# Schematic.net
KiCad netlist of a schematic drawn in EasyEDA
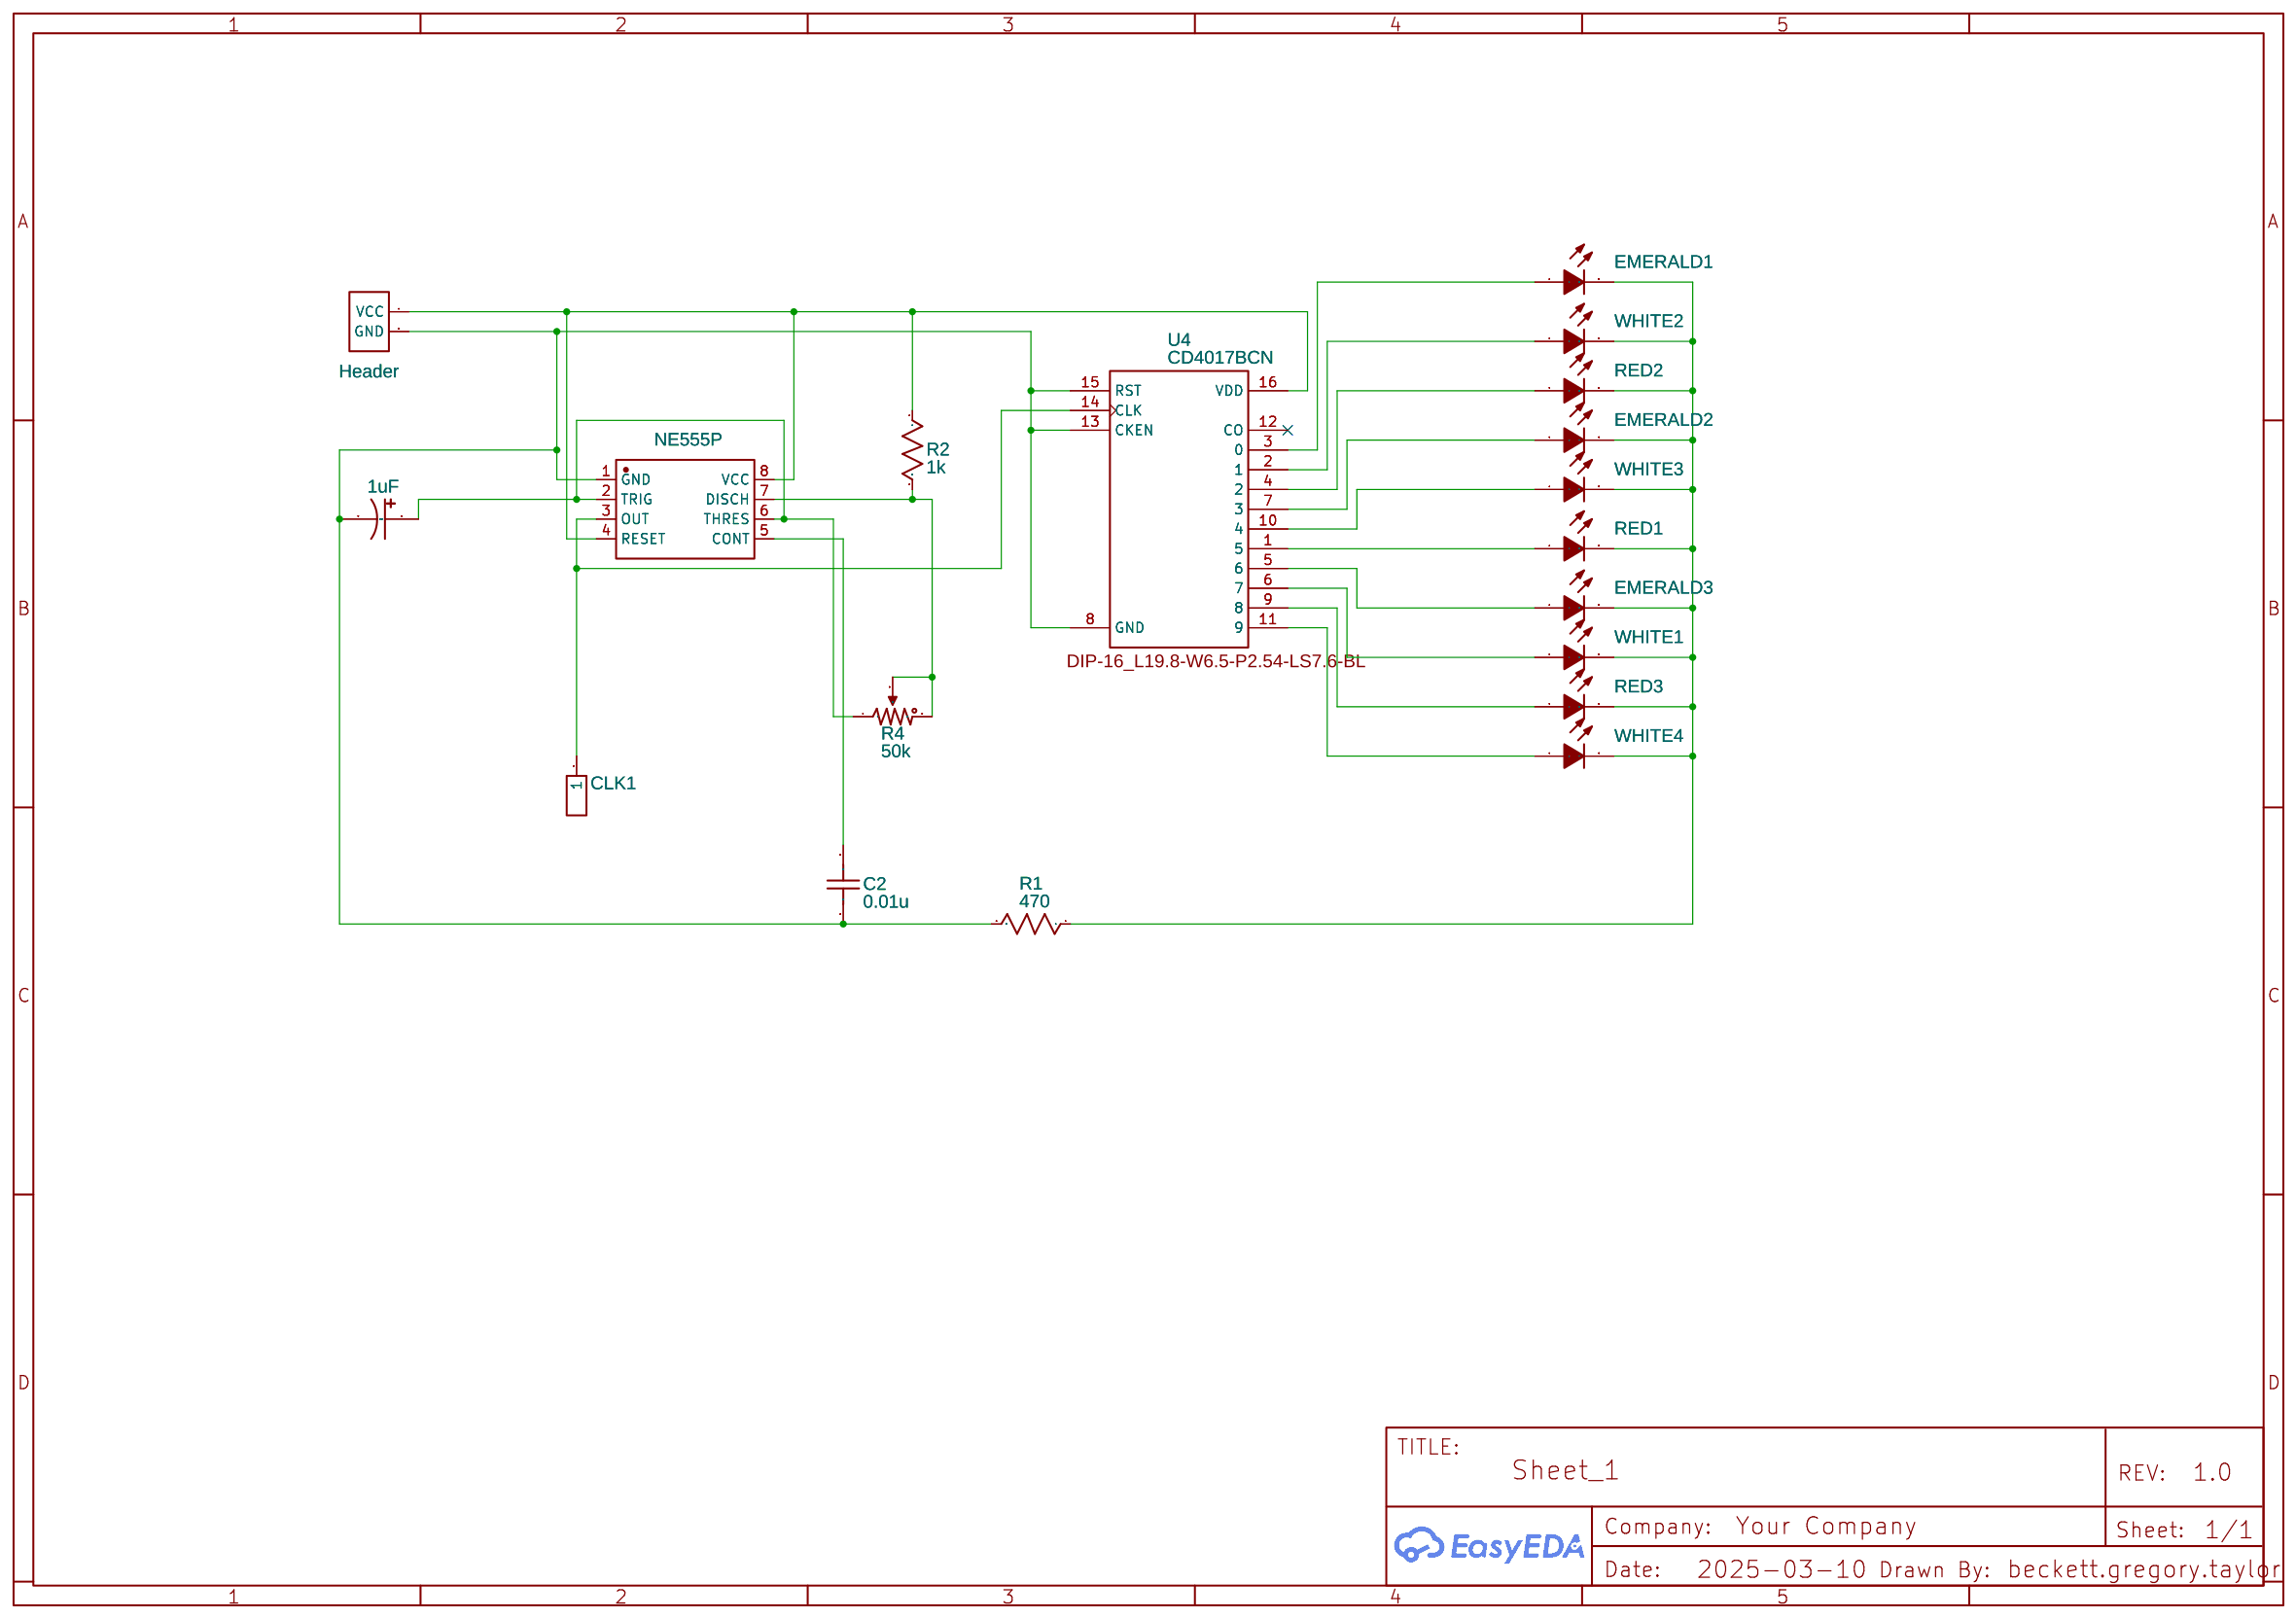
[diagram p0: schematic sheet]

(export (version "E")
  (design (tool "Eeschema 10.0.6"))
  (components
    (comp (ref "C1")
      (value "1uF")
      (fields (field (name "Manufacturer Part") "UVZ1H010MDD") (field (name "Manufacturer") "Nichicon(尼吉康)"))
      (libsource (lib "") (part "UVZ1H010MDD"))
    )
    (comp (ref "C2") (value "0.01u") (libsource (lib "") (part "C_0603_US")))
    (comp (ref "CLK1")
      (value "C81276")
      (fields
        (field (name "Manufacturer Part") "2.54-1*1P针")
        (field (name "Manufacturer") "BOOMELE(Boom Precision Elec)")
      )
      (libsource (lib "") (part "Header-Male-2.54_1x1"))
    )
    (comp (ref "EMERALD1") (value "LED_5MM") (libsource (lib "") (part "LED_5MM_2")))
    (comp (ref "EMERALD2") (value "LED_5MM") (libsource (lib "") (part "LED_5MM_2")))
    (comp (ref "EMERALD3") (value "LED_5MM") (libsource (lib "") (part "LED_5MM_2")))
    (comp (ref "H1") (value "Header") (libsource (lib "") (part "HEADER-FEMALE-2.54_1X2")))
    (comp (ref "R1")
      (value "470")
      (fields (field (name "Manufacturer Part") "?"))
      (libsource (lib "") (part "Resistor_1"))
    )
    (comp (ref "R2")
      (value "1k")
      (fields (field (name "Manufacturer Part") "?"))
      (libsource (lib "") (part "Resistor"))
    )
    (comp (ref "R4")
      (value "50k")
      (fields (field (name "Manufacturer Part") "?"))
      (libsource (lib "") (part "Potentiometer"))
    )
    (comp (ref "RED1") (value "LED_5MM") (libsource (lib "") (part "LED_5MM_1")))
    (comp (ref "RED2") (value "LED_5MM") (libsource (lib "") (part "LED_5MM_1")))
    (comp (ref "RED3") (value "LED_5MM") (libsource (lib "") (part "LED_5MM_1")))
    (comp (ref "U2")
      (value "NE555P")
      (fields (field (name "Manufacturer") "TI(德州仪器)"))
      (libsource (lib "") (part "NE555P"))
    )
    (comp (ref "U4") (value "CD4017BCN") (libsource (lib "") (part "CD4017BCN")))
    (comp (ref "WHITE1") (value "LED_5MM") (libsource (lib "") (part "LED_5MM")))
    (comp (ref "WHITE2") (value "LED_5MM") (libsource (lib "") (part "LED_5MM")))
    (comp (ref "WHITE3") (value "LED_5MM") (libsource (lib "") (part "LED_5MM")))
    (comp (ref "WHITE4") (value "LED_5MM") (libsource (lib "") (part "LED_5MM")))
  )
  (nets
    (net (code "1") (name "Net-(EMERALD1-A)") (class "Default")
      (node (ref "EMERALD1") (pin "1") (pinfunction "A_1") (pintype "input"))
      (node (ref "U4") (pin "3") (pinfunction "0_3") (pintype "output"))
    )
    (net (code "2") (name "Net-(EMERALD1-K)") (class "Default")
      (node (ref "EMERALD1") (pin "2") (pinfunction "K_2") (pintype "input"))
      (node (ref "EMERALD2") (pin "2") (pinfunction "K_2") (pintype "input"))
      (node (ref "EMERALD3") (pin "2") (pinfunction "K_2") (pintype "input"))
      (node (ref "R1") (pin "1") (pinfunction "1_1") (pintype "unspecified"))
      (node (ref "RED1") (pin "2") (pinfunction "K_2") (pintype "input"))
      (node (ref "RED2") (pin "2") (pinfunction "K_2") (pintype "input"))
      (node (ref "RED3") (pin "2") (pinfunction "K_2") (pintype "input"))
      (node (ref "WHITE1") (pin "2") (pinfunction "K_2") (pintype "input"))
      (node (ref "WHITE2") (pin "2") (pinfunction "K_2") (pintype "input"))
      (node (ref "WHITE3") (pin "2") (pinfunction "K_2") (pintype "input"))
      (node (ref "WHITE4") (pin "2") (pinfunction "K_2") (pintype "input"))
    )
    (net (code "3") (name "Net-(EMERALD2-A)") (class "Default")
      (node (ref "EMERALD2") (pin "1") (pinfunction "A_1") (pintype "input"))
      (node (ref "U4") (pin "7") (pinfunction "3_7") (pintype "output"))
    )
    (net (code "4") (name "Net-(EMERALD3-A)") (class "Default")
      (node (ref "EMERALD3") (pin "1") (pinfunction "A_1") (pintype "input"))
      (node (ref "U4") (pin "5") (pinfunction "6_5") (pintype "output"))
    )
    (net (code "5") (name "Net-(H1-GND)") (class "Default")
      (node (ref "C1") (pin "2") (pinfunction "2_2") (pintype "unspecified"))
      (node (ref "C2") (pin "1") (pinfunction "1_1") (pintype "unspecified"))
      (node (ref "H1") (pin "2") (pinfunction "GND_2") (pintype "unspecified"))
      (node (ref "R1") (pin "2") (pinfunction "2_2") (pintype "unspecified"))
      (node (ref "U2") (pin "1") (pinfunction "GND_1") (pintype "unspecified"))
      (node (ref "U4") (pin "13") (pinfunction "CKEN_13") (pintype "unspecified"))
      (node (ref "U4") (pin "15") (pinfunction "RST_15") (pintype "unspecified"))
      (node (ref "U4") (pin "8") (pinfunction "GND_8") (pintype "passive"))
    )
    (net (code "6") (name "Net-(H1-VCC)") (class "Default")
      (node (ref "H1") (pin "1") (pinfunction "VCC_1") (pintype "unspecified"))
      (node (ref "R2") (pin "1") (pinfunction "1_1") (pintype "unspecified"))
      (node (ref "U2") (pin "4") (pinfunction "RESET_4") (pintype "unspecified"))
      (node (ref "U2") (pin "8") (pinfunction "VCC_8") (pintype "unspecified"))
      (node (ref "U4") (pin "16") (pinfunction "VDD_16") (pintype "passive"))
    )
    (net (code "7") (name "Net-(R4-2)") (class "Default")
      (node (ref "R2") (pin "2") (pinfunction "2_2") (pintype "unspecified"))
      (node (ref "R4") (pin "2") (pinfunction "3_2") (pintype "unspecified"))
      (node (ref "R4") (pin "3") (pinfunction "2_3") (pintype "unspecified"))
      (node (ref "U2") (pin "7") (pinfunction "DISCH_7") (pintype "unspecified"))
    )
    (net (code "8") (name "Net-(RED1-A)") (class "Default")
      (node (ref "RED1") (pin "1") (pinfunction "A_1") (pintype "input"))
      (node (ref "U4") (pin "1") (pinfunction "5_1") (pintype "output"))
    )
    (net (code "9") (name "Net-(RED2-A)") (class "Default")
      (node (ref "RED2") (pin "1") (pinfunction "A_1") (pintype "input"))
      (node (ref "U4") (pin "4") (pinfunction "2_4") (pintype "output"))
    )
    (net (code "10") (name "Net-(RED3-A)") (class "Default")
      (node (ref "RED3") (pin "1") (pinfunction "A_1") (pintype "input"))
      (node (ref "U4") (pin "9") (pinfunction "8_9") (pintype "output"))
    )
    (net (code "11") (name "Net-(U2-CONT)") (class "Default")
      (node (ref "C2") (pin "2") (pinfunction "2_2") (pintype "unspecified"))
      (node (ref "U2") (pin "5") (pinfunction "CONT_5") (pintype "unspecified"))
    )
    (net (code "12") (name "Net-(U2-OUT)") (class "Default")
      (node (ref "CLK1") (pin "1") (pinfunction "1_1") (pintype "unspecified"))
      (node (ref "U2") (pin "3") (pinfunction "OUT_3") (pintype "unspecified"))
      (node (ref "U4") (pin "14") (pinfunction "CLK_14") (pintype "unspecified"))
    )
    (net (code "13") (name "Net-(U2-THRES)") (class "Default")
      (node (ref "C1") (pin "1") (pinfunction "1_1") (pintype "unspecified"))
      (node (ref "R4") (pin "1") (pinfunction "1_1") (pintype "unspecified"))
      (node (ref "U2") (pin "2") (pinfunction "TRIG_2") (pintype "unspecified"))
      (node (ref "U2") (pin "6") (pinfunction "THRES_6") (pintype "unspecified"))
    )
    (net (code "14") (name "Net-(U4-1)") (class "Default")
      (node (ref "U4") (pin "2") (pinfunction "1_2") (pintype "output"))
      (node (ref "WHITE2") (pin "1") (pinfunction "A_1") (pintype "input"))
    )
    (net (code "15") (name "Net-(U4-4)") (class "Default")
      (node (ref "U4") (pin "10") (pinfunction "4_10") (pintype "output"))
      (node (ref "WHITE3") (pin "1") (pinfunction "A_1") (pintype "input"))
    )
    (net (code "16") (name "Net-(U4-7)") (class "Default")
      (node (ref "U4") (pin "6") (pinfunction "7_6") (pintype "output"))
      (node (ref "WHITE1") (pin "1") (pinfunction "A_1") (pintype "input"))
    )
    (net (code "17") (name "Net-(U4-9)") (class "Default")
      (node (ref "U4") (pin "11") (pinfunction "9_11") (pintype "output"))
      (node (ref "WHITE4") (pin "1") (pinfunction "A_1") (pintype "input"))
    )
    (net (code "18") (name "unconnected-(U4-CO-Pad12)") (class "Default")
      (node (ref "U4") (pin "12") (pinfunction "CO_12") (pintype "output+no_connect"))
    )
  )
)
